# battery-charging.net
KiCad netlist of a schematic drawn in Altium Designer
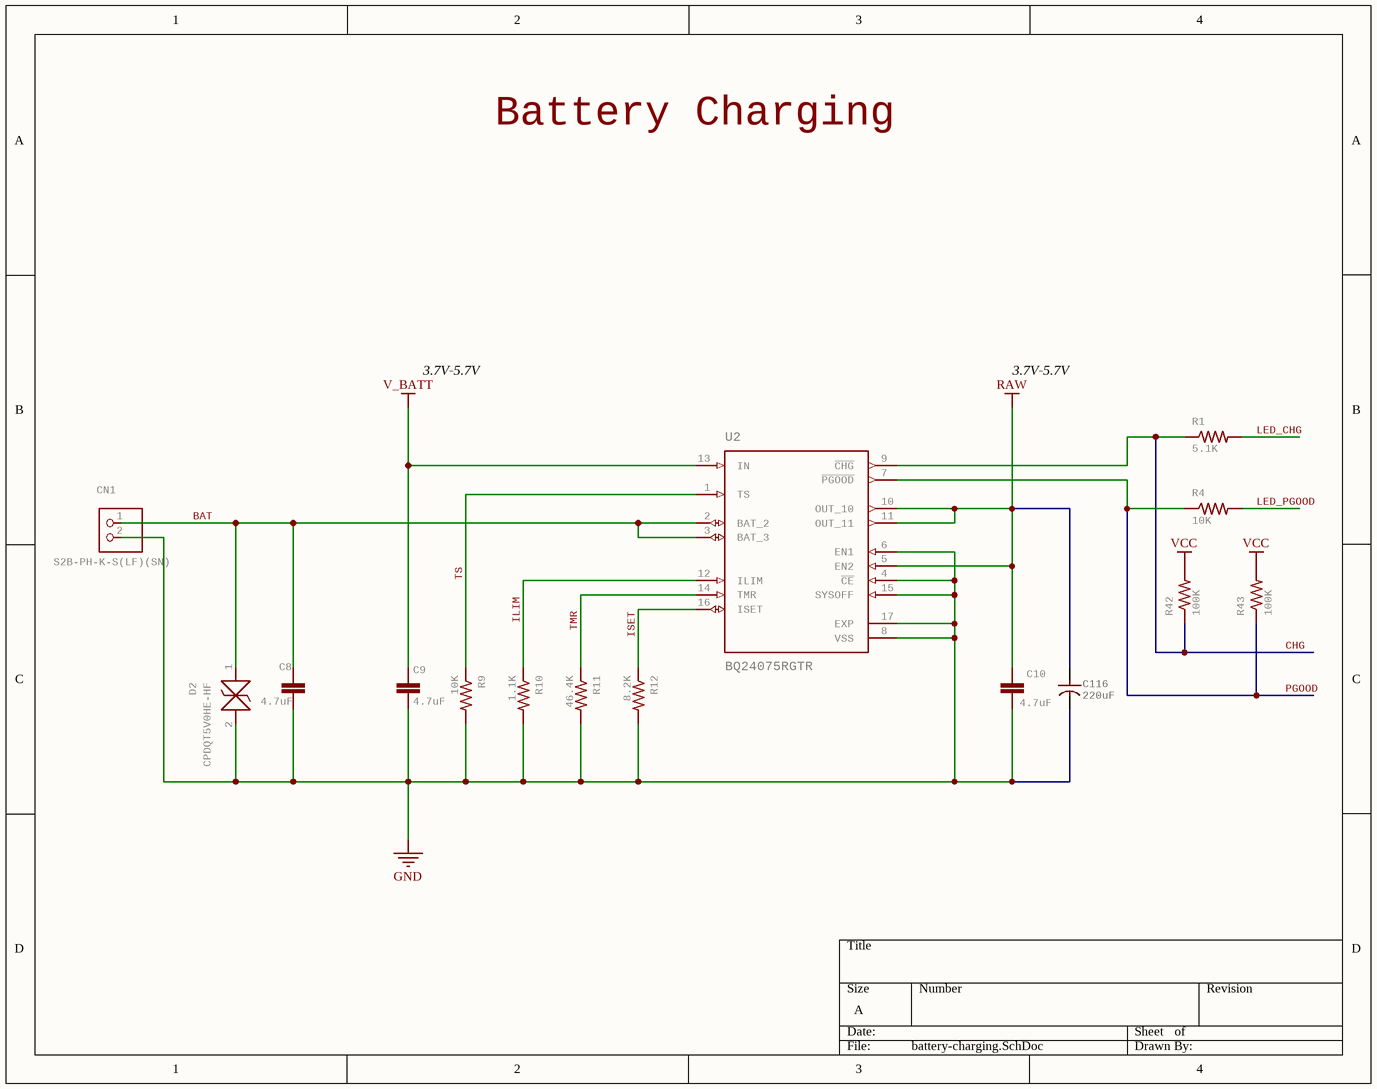
[diagram p0: battery-charging.SchDoc]

(export (version "E")
  (design (tool "Eeschema 10.0.6"))
  (components
    (comp (ref "C8")
      (value "4.7uF")
      (footprint "0402-CAP")
      (description "CapacitorStandard 0603 ceramic capacitor, and 0.1\" leaded capacitor.")
      (fields (field (name "MPN") "JMK105BBJ475MV-F"))
      (libsource (lib "rt10") (part "CAP0402-CAP"))
    )
    (comp (ref "C9")
      (value "4.7uF")
      (footprint "0402-CAP")
      (description "CapacitorStandard 0603 ceramic capacitor, and 0.1\" leaded capacitor.")
      (fields (field (name "MPN") "JMK105BBJ475MV-F"))
      (libsource (lib "rt10") (part "CAP0402-CAP"))
    )
    (comp (ref "C10")
      (value "4.7uF")
      (footprint "0402-CAP")
      (description "CapacitorStandard 0603 ceramic capacitor, and 0.1\" leaded capacitor.")
      (fields (field (name "MPN") "JMK105BBJ475MV-F"))
      (libsource (lib "rt10") (part "CAP0402-CAP"))
    )
    (comp (ref "C116")
      (value "220uF")
      (footprint "CAP-TANT-1411")
      (fields (field (name "PART NUMBER") "F930J227MBA"))
      (libsource (lib "rt10") (part "CAP_POL"))
    )
    (comp (ref "CN1")
      (value "S2B-PH-K-S(LF)(SN)")
      (footprint "JST-PH-2-THM-RA")
      (fields (field (name "LIBRARYNAME") "adafruit-updated"))
      (libsource (lib "rt10") (part "JST_2PIN-THM-RA"))
    )
    (comp (ref "D2")
      (value "CPDQT5V0HE-HF")
      (footprint "CPDQT5V0HEHF")
      (description "ESD Suppressors / TVS Diodes DIODE ESD 5VWM 65W 0402/SOD-923F   Source:  Datasheet")
      (fields (field (name "MOUSER_PART_NUMBER") "MOUSER_PART_NUMBER"))
      (libsource (lib "rt10") (part "CPDQT5V0HE-HF"))
    )
    (comp (ref "R1")
      (value "5.1K")
      (footprint "0402-RES")
      (description "ResistorBasic schematic elements and footprints for 0603, 1206, and PTH resistors.")
      (fields (field (name "MPN") "RC0402JR-075K1L"))
      (libsource (lib "rt10") (part "RESISTOR0402-RES"))
    )
    (comp (ref "R4")
      (value "10K")
      (footprint "0402-RES")
      (description "ResistorBasic schematic elements and footprints for 0603, 1206, and PTH resistors.")
      (fields (field (name "MPN") "AC0402FR-1310KL"))
      (libsource (lib "rt10") (part "RESISTOR0402-RES"))
    )
    (comp (ref "R9")
      (value "10K")
      (footprint "0402-RES")
      (description "ResistorBasic schematic elements and footprints for 0603, 1206, and PTH resistors.")
      (fields (field (name "MPN") "AC0402FR-1310KL"))
      (libsource (lib "rt10") (part "RESISTOR0402-RES"))
    )
    (comp (ref "R10")
      (value "1.1K")
      (footprint "0402-RES")
      (description "ResistorBasic schematic elements and footprints for 0603, 1206, and PTH resistors.")
      (fields (field (name "MPN") "RC0402JR-071K1"))
      (libsource (lib "rt10") (part "RESISTOR0402-RES"))
    )
    (comp (ref "R11")
      (value "46.4K")
      (footprint "0402-RES")
      (description "ResistorBasic schematic elements and footprints for 0603, 1206, and PTH resistors.")
      (fields (field (name "MPN") "WR04X4642FTL"))
      (libsource (lib "rt10") (part "RESISTOR0402-RES"))
    )
    (comp (ref "R12")
      (value "8.2K")
      (footprint "0402-RES")
      (description "ResistorBasic schematic elements and footprints for 0603, 1206, and PTH resistors.")
      (fields (field (name "MPN") "CR0402-FX-8201GLF"))
      (libsource (lib "rt10") (part "RESISTOR0402-RES"))
    )
    (comp (ref "R42")
      (value "100K")
      (footprint "0402-RES")
      (description "ResistorBasic schematic elements and footprints for 0603, 1206, and PTH resistors.")
      (fields (field (name "MPN") "AC0402FR-07100KL"))
      (libsource (lib "rt10") (part "RESISTOR0402-RES"))
    )
    (comp (ref "R43")
      (value "100K")
      (footprint "0402-RES")
      (description "ResistorBasic schematic elements and footprints for 0603, 1206, and PTH resistors.")
      (fields (field (name "MPN") "AC0402FR-07100KL"))
      (libsource (lib "rt10") (part "RESISTOR0402-RES"))
    )
    (comp (ref "U2")
      (value "BQ24075RGTR")
      (footprint "QFN50P300X300X100-17N")
      (fields (field (name "MF") "Texas Instruments"))
      (libsource (lib "rt10") (part "BQ24075RGTR"))
    )
  )
  (nets
    (net (code "1") (name "/BAT") (class "Default")
      (node (ref "C8") (pin "2") (pinfunction "2_2") (pintype "passive"))
      (node (ref "CN1") (pin "1") (pinfunction "2_1") (pintype "passive"))
      (node (ref "D2") (pin "1") (pinfunction "1_1") (pintype "bidirectional"))
      (node (ref "U2") (pin "2") (pinfunction "BAT_2_2") (pintype "bidirectional"))
      (node (ref "U2") (pin "3") (pinfunction "BAT_3_3") (pintype "bidirectional"))
    )
    (net (code "2") (name "/CHG") (class "Default")
      (node (ref "R1") (pin "1") (pinfunction "1_1") (pintype "passive"))
      (node (ref "R42") (pin "1") (pinfunction "1_1") (pintype "passive"))
      (node (ref "U2") (pin "9") (pinfunction "~{CHG}_9") (pintype "output"))
    )
    (net (code "3") (name "/ILIM") (class "Default")
      (node (ref "R10") (pin "1") (pinfunction "1_1") (pintype "passive"))
      (node (ref "U2") (pin "12") (pinfunction "ILIM_12") (pintype "input"))
    )
    (net (code "4") (name "/ISET") (class "Default")
      (node (ref "R12") (pin "1") (pinfunction "1_1") (pintype "passive"))
      (node (ref "U2") (pin "16") (pinfunction "ISET_16") (pintype "bidirectional"))
    )
    (net (code "5") (name "/LED_CHG") (class "Default")
      (node (ref "R1") (pin "2") (pinfunction "2_2") (pintype "passive"))
    )
    (net (code "6") (name "/LED_PGOOD") (class "Default")
      (node (ref "R4") (pin "2") (pinfunction "2_2") (pintype "passive"))
    )
    (net (code "7") (name "/PGOOD") (class "Default")
      (node (ref "R4") (pin "1") (pinfunction "1_1") (pintype "passive"))
      (node (ref "R43") (pin "1") (pinfunction "1_1") (pintype "passive"))
      (node (ref "U2") (pin "7") (pinfunction "~{PGOOD}_7") (pintype "output"))
    )
    (net (code "8") (name "/TMR") (class "Default")
      (node (ref "R11") (pin "1") (pinfunction "1_1") (pintype "passive"))
      (node (ref "U2") (pin "14") (pinfunction "TMR_14") (pintype "input"))
    )
    (net (code "9") (name "/TS") (class "Default")
      (node (ref "R9") (pin "1") (pinfunction "1_1") (pintype "passive"))
      (node (ref "U2") (pin "1") (pinfunction "TS_1") (pintype "input"))
    )
    (net (code "10") (name "GND") (class "Default")
      (node (ref "C10") (pin "1") (pinfunction "1_1") (pintype "passive"))
      (node (ref "C116") (pin "2") (pinfunction "2_2") (pintype "passive"))
      (node (ref "C8") (pin "1") (pinfunction "1_1") (pintype "passive"))
      (node (ref "C9") (pin "1") (pinfunction "1_1") (pintype "passive"))
      (node (ref "CN1") (pin "2") (pinfunction "1_2") (pintype "passive"))
      (node (ref "D2") (pin "2") (pinfunction "2_2") (pintype "bidirectional"))
      (node (ref "R10") (pin "2") (pinfunction "2_2") (pintype "passive"))
      (node (ref "R11") (pin "2") (pinfunction "2_2") (pintype "passive"))
      (node (ref "R12") (pin "2") (pinfunction "2_2") (pintype "passive"))
      (node (ref "R9") (pin "2") (pinfunction "2_2") (pintype "passive"))
      (node (ref "U2") (pin "15") (pinfunction "SYSOFF_15") (pintype "input"))
      (node (ref "U2") (pin "17") (pinfunction "EXP_17") (pintype "power_in"))
      (node (ref "U2") (pin "4") (pinfunction "~{CE}_4") (pintype "input"))
      (node (ref "U2") (pin "6") (pinfunction "EN1_6") (pintype "input"))
      (node (ref "U2") (pin "8") (pinfunction "VSS_8") (pintype "power_in"))
    )
    (net (code "11") (name "RAW") (class "Default")
      (node (ref "C10") (pin "2") (pinfunction "2_2") (pintype "passive"))
      (node (ref "C116") (pin "1") (pinfunction "1_1") (pintype "passive"))
      (node (ref "U2") (pin "10") (pinfunction "OUT_10_10") (pintype "output"))
      (node (ref "U2") (pin "11") (pinfunction "OUT_11_11") (pintype "output"))
      (node (ref "U2") (pin "5") (pinfunction "EN2_5") (pintype "input"))
    )
    (net (code "12") (name "VCC") (class "Default")
      (node (ref "R42") (pin "2") (pinfunction "2_2") (pintype "passive"))
      (node (ref "R43") (pin "2") (pinfunction "2_2") (pintype "passive"))
    )
    (net (code "13") (name "V_BATT") (class "Default")
      (node (ref "C9") (pin "2") (pinfunction "2_2") (pintype "passive"))
      (node (ref "U2") (pin "13") (pinfunction "IN_13") (pintype "input"))
    )
  )
)
